# metaPixel-Controller.net
KiCad netlist of a schematic drawn in EAGLE
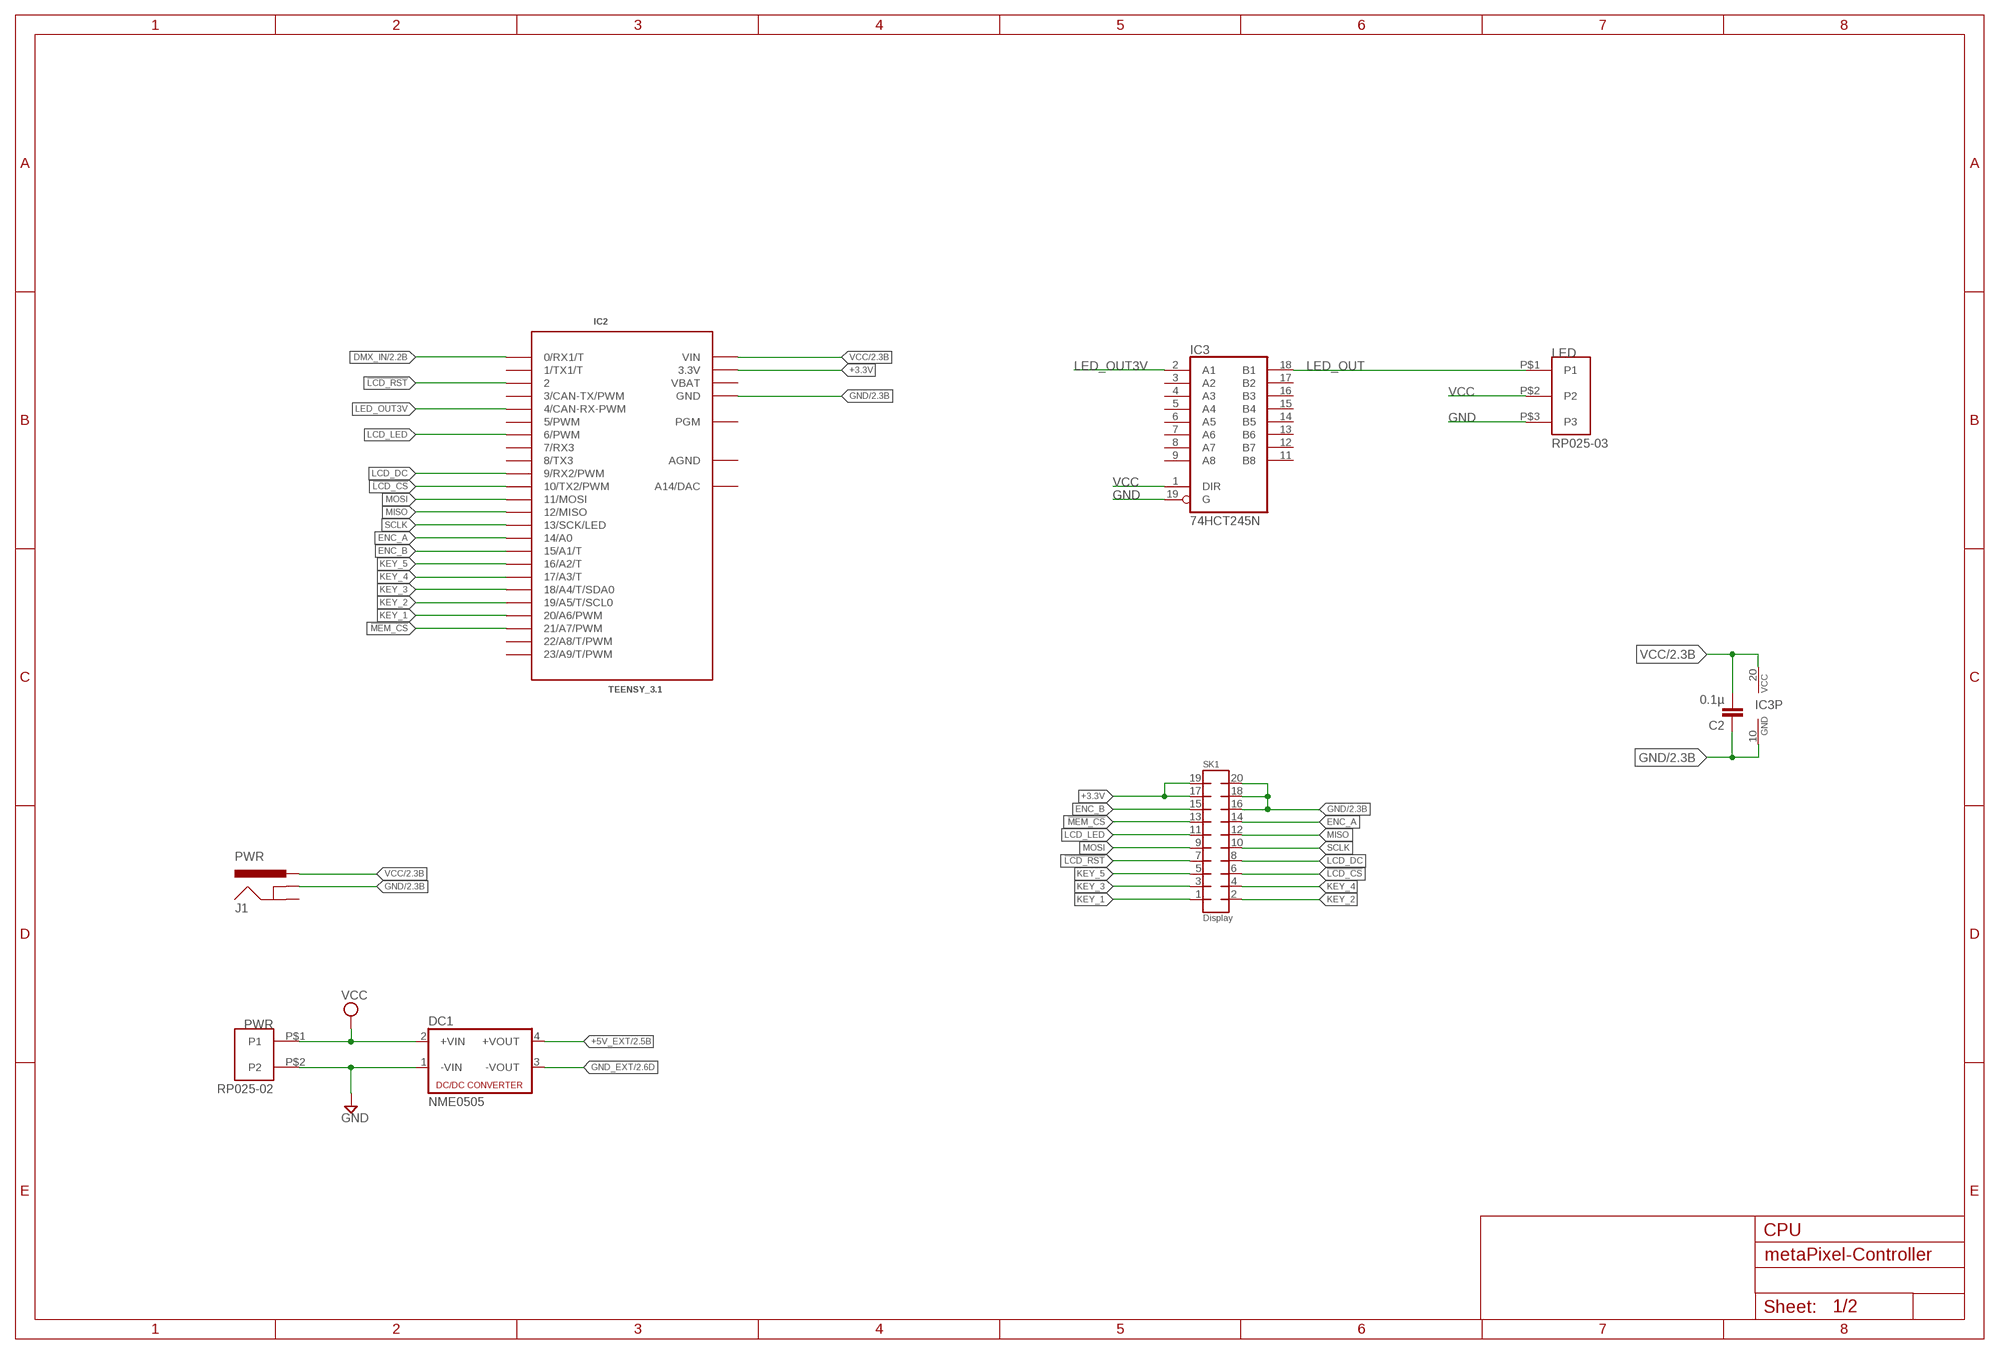
[diagram p0: schematic, sheet 1]
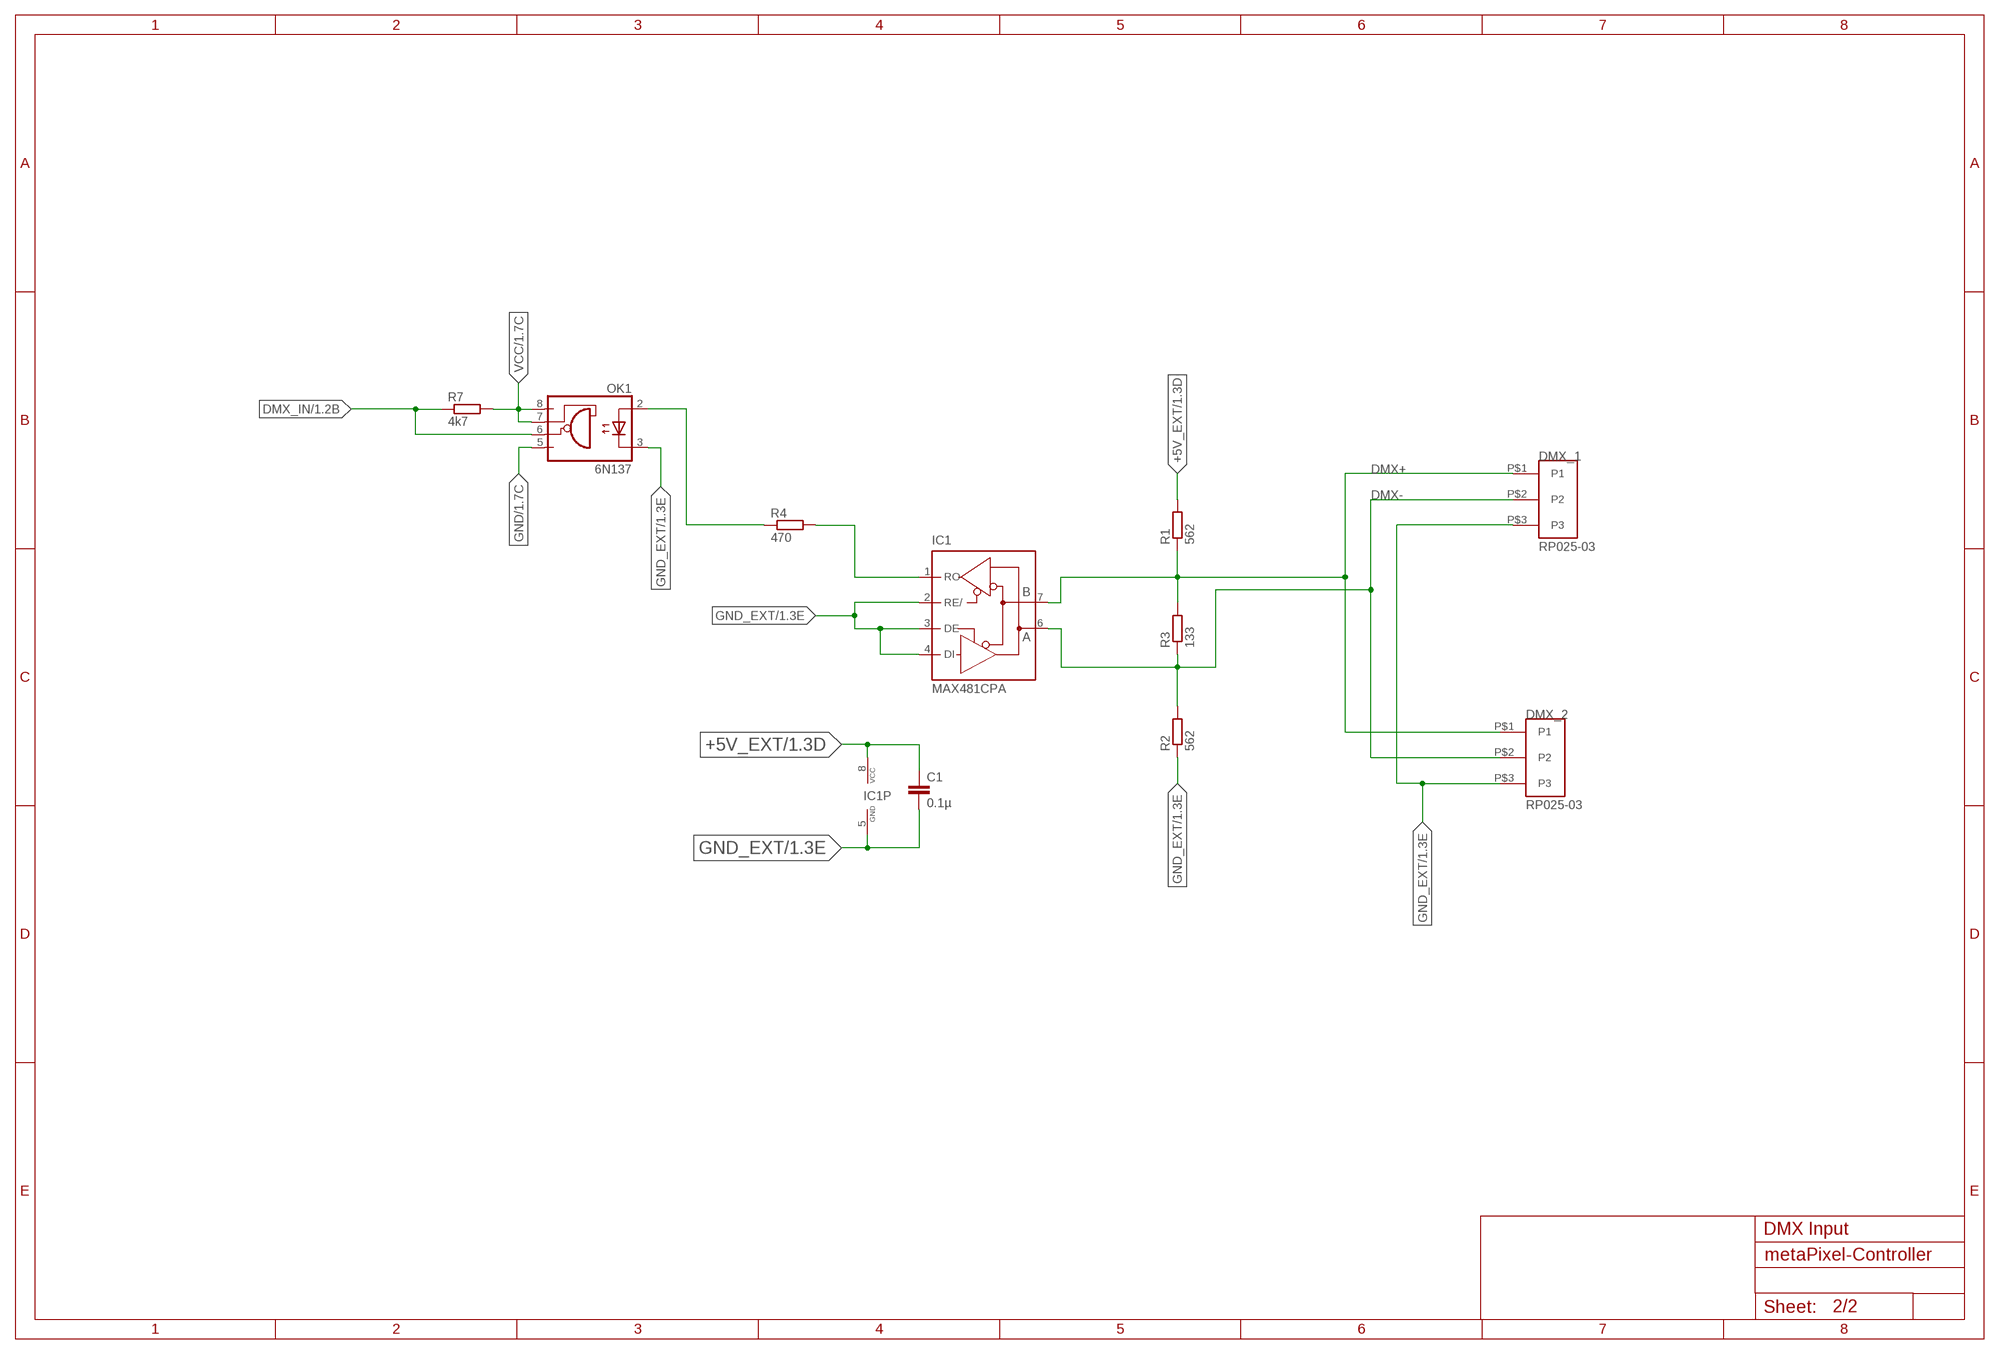
[diagram p1: schematic, sheet 2]

(export (version "E")
  (design (tool "Eeschema 10.0.6"))
  (components
    (comp (ref "C2")
      (value "0.1µ")
      (footprint "eagle-import:C025-030X050")
      (libsource (lib "eagle-import") (part "C-EU025-030X050"))
    )
    (comp (ref "DC1")
      (value "NME0505")
      (footprint "eagle-import:NME")
      (fields (field (name "MF") "C & D TECHNOLOGIES, INC") (field (name "MPN") "NME1205D"))
      (libsource (lib "eagle-import") (part "NME"))
    )
    (comp (ref "IC2")
      (value "TEENSY_3.1")
      (footprint "eagle-import:TEENSY3-OUTER_ROW")
      (libsource (lib "eagle-import") (part "TEENSY_3.1_OUTER_ROW"))
    )
    (comp (ref "IC3")
      (value "74HCT245N")
      (footprint "eagle-import:DIL20")
      (libsource (lib "eagle-import") (part "74245NHCT"))
    )
    (comp (ref "J1")
      (value "PWR")
      (footprint "eagle-import:POWER_JACK_SLOT")
      (libsource (lib "eagle-import") (part "POWER_JACKSLT"))
    )
    (comp (ref "LED")
      (value "RP025-03")
      (footprint "eagle-import:RP025-03")
      (libsource (lib "eagle-import") (part "RP025-03"))
    )
    (comp (ref "PWR")
      (value "RP025-02")
      (footprint "eagle-import:RP025-02")
      (libsource (lib "eagle-import") (part "RP025-02"))
    )
    (comp (ref "SK1")
      (value "Display")
      (footprint "eagle-import:AMP-215079-20")
      (libsource (lib "eagle-import") (part "MMATCH-20-PTH"))
    )
    (comp (ref "C1")
      (value "0.1µ")
      (footprint "eagle-import:C025-030X050")
      (libsource (lib "eagle-import") (part "C-EU025-030X050"))
    )
    (comp (ref "DMX_1")
      (value "RP025-03")
      (footprint "eagle-import:RP025-03")
      (libsource (lib "eagle-import") (part "RP025-03"))
    )
    (comp (ref "DMX_2")
      (value "RP025-03")
      (footprint "eagle-import:RP025-03")
      (libsource (lib "eagle-import") (part "RP025-03"))
    )
    (comp (ref "IC1")
      (value "MAX481CPA")
      (footprint "eagle-import:DIL08")
      (fields (field (name "MPN") "MAX481CPA+"))
      (libsource (lib "eagle-import") (part "MAX481CPA"))
    )
    (comp (ref "OK1")
      (value "6N137")
      (footprint "eagle-import:DIL08")
      (libsource (lib "eagle-import") (part "6N137"))
    )
    (comp (ref "R1")
      (value "562")
      (footprint "eagle-import:0207_7")
      (libsource (lib "eagle-import") (part "resistor_R-EU_0207/7"))
    )
    (comp (ref "R2")
      (value "562")
      (footprint "eagle-import:0207_7")
      (libsource (lib "eagle-import") (part "resistor_R-EU_0207/7"))
    )
    (comp (ref "R3")
      (value "133")
      (footprint "eagle-import:0207_7")
      (libsource (lib "eagle-import") (part "resistor_R-EU_0207/7"))
    )
    (comp (ref "R4")
      (value "470")
      (footprint "eagle-import:0207_10")
      (libsource (lib "eagle-import") (part "R-EU_0207/10"))
    )
    (comp (ref "R7")
      (value "4k7")
      (footprint "eagle-import:0207_10")
      (libsource (lib "eagle-import") (part "resistor_R-EU_0207/10"))
    )
  )
  (nets
    (net (code "1") (name "+3.3V") (class "Default")
      (node (ref "IC2") (pin "3.3V") (pinfunction "3.3V_3.3V") (pintype "power_in"))
      (node (ref "IC2") (pin "3.3V1") (pinfunction "3.3V_3.3V1") (pintype "power_in"))
      (node (ref "SK1") (pin "17") (pinfunction "17_17") (pintype "bidirectional"))
      (node (ref "SK1") (pin "19") (pinfunction "19_19") (pintype "bidirectional"))
    )
    (net (code "2") (name "+5V_EXT") (class "Default")
      (node (ref "C1") (pin "1") (pinfunction "1_1") (pintype "passive"))
      (node (ref "DC1") (pin "4") (pinfunction "+VOUT_4") (pintype "passive"))
      (node (ref "IC1") (pin "8") (pinfunction "VCC_8") (pintype "power_in"))
      (node (ref "R1") (pin "2") (pinfunction "2_2") (pintype "passive"))
    )
    (net (code "3") (name "AGND") (class "Default")
      (node (ref "IC2") (pin "AGND") (pinfunction "AGND_AGND") (pintype "power_in"))
    )
    (net (code "4") (name "DMX+") (class "Default")
      (node (ref "DMX_1") (pin "P$1") (pinfunction "P1_P$1") (pintype "bidirectional"))
      (node (ref "DMX_2") (pin "P$1") (pinfunction "P1_P$1") (pintype "bidirectional"))
      (node (ref "IC1") (pin "7") (pinfunction "B_7") (pintype "passive"))
      (node (ref "R1") (pin "1") (pinfunction "1_1") (pintype "passive"))
      (node (ref "R3") (pin "2") (pinfunction "2_2") (pintype "passive"))
    )
    (net (code "5") (name "DMX-") (class "Default")
      (node (ref "DMX_1") (pin "P$2") (pinfunction "P2_P$2") (pintype "bidirectional"))
      (node (ref "DMX_2") (pin "P$2") (pinfunction "P2_P$2") (pintype "bidirectional"))
      (node (ref "IC1") (pin "6") (pinfunction "A_6") (pintype "passive"))
      (node (ref "R2") (pin "2") (pinfunction "2_2") (pintype "passive"))
      (node (ref "R3") (pin "1") (pinfunction "1_1") (pintype "passive"))
    )
    (net (code "6") (name "DMX_IN") (class "Default")
      (node (ref "IC2") (pin "0") (pinfunction "0/RX1/T_0") (pintype "bidirectional"))
      (node (ref "OK1") (pin "6") (pinfunction "VO_6") (pintype "passive"))
      (node (ref "R7") (pin "1") (pinfunction "1_1") (pintype "passive"))
    )
    (net (code "7") (name "ENC_A") (class "Default")
      (node (ref "IC2") (pin "14/A0") (pinfunction "14/A0_14/A0") (pintype "bidirectional"))
      (node (ref "SK1") (pin "14") (pinfunction "14_14") (pintype "bidirectional"))
    )
    (net (code "8") (name "ENC_B") (class "Default")
      (node (ref "IC2") (pin "15/A1") (pinfunction "15/A1/T_15/A1") (pintype "bidirectional"))
      (node (ref "SK1") (pin "15") (pinfunction "15_15") (pintype "bidirectional"))
    )
    (net (code "9") (name "GND") (class "Default")
      (node (ref "C2") (pin "1") (pinfunction "1_1") (pintype "passive"))
      (node (ref "DC1") (pin "1") (pinfunction "-VIN_1") (pintype "passive"))
      (node (ref "IC2") (pin "GND") (pinfunction "GND_GND") (pintype "power_in"))
      (node (ref "IC2") (pin "GND1") (pinfunction "GND_GND1") (pintype "power_in"))
      (node (ref "IC3") (pin "10") (pinfunction "GND_10") (pintype "power_in"))
      (node (ref "IC3") (pin "19") (pinfunction "G_19") (pintype "input"))
      (node (ref "J1") (pin "GND@1") (pinfunction "GNDBREAK_GND@1") (pintype "bidirectional"))
      (node (ref "LED") (pin "P$3") (pinfunction "P3_P$3") (pintype "bidirectional"))
      (node (ref "OK1") (pin "5") (pinfunction "GND_5") (pintype "passive"))
      (node (ref "PWR") (pin "P$2") (pinfunction "P2_P$2") (pintype "bidirectional"))
      (node (ref "SK1") (pin "16") (pinfunction "16_16") (pintype "bidirectional"))
      (node (ref "SK1") (pin "18") (pinfunction "18_18") (pintype "bidirectional"))
      (node (ref "SK1") (pin "20") (pinfunction "20_20") (pintype "bidirectional"))
    )
    (net (code "10") (name "GND_EXT") (class "Default")
      (node (ref "C1") (pin "2") (pinfunction "2_2") (pintype "passive"))
      (node (ref "DC1") (pin "3") (pinfunction "-VOUT_3") (pintype "passive"))
      (node (ref "DMX_1") (pin "P$3") (pinfunction "P3_P$3") (pintype "bidirectional"))
      (node (ref "DMX_2") (pin "P$3") (pinfunction "P3_P$3") (pintype "bidirectional"))
      (node (ref "IC1") (pin "2") (pinfunction "RE/_2") (pintype "input"))
      (node (ref "IC1") (pin "3") (pinfunction "DE_3") (pintype "input"))
      (node (ref "IC1") (pin "4") (pinfunction "DI_4") (pintype "input"))
      (node (ref "IC1") (pin "5") (pinfunction "GND_5") (pintype "power_in"))
      (node (ref "OK1") (pin "3") (pinfunction "C_3") (pintype "passive"))
      (node (ref "R2") (pin "1") (pinfunction "1_1") (pintype "passive"))
    )
    (net (code "11") (name "KEY_1") (class "Default")
      (node (ref "IC2") (pin "20/A6") (pinfunction "20/A6/PWM_20/A6") (pintype "bidirectional"))
      (node (ref "SK1") (pin "1") (pinfunction "1_1") (pintype "bidirectional"))
    )
    (net (code "12") (name "KEY_2") (class "Default")
      (node (ref "IC2") (pin "19/A5") (pinfunction "19/A5/T/SCL0_19/A5") (pintype "bidirectional"))
      (node (ref "SK1") (pin "2") (pinfunction "2_2") (pintype "bidirectional"))
    )
    (net (code "13") (name "KEY_3") (class "Default")
      (node (ref "IC2") (pin "18/A4") (pinfunction "18/A4/T/SDA0_18/A4") (pintype "bidirectional"))
      (node (ref "SK1") (pin "3") (pinfunction "3_3") (pintype "bidirectional"))
    )
    (net (code "14") (name "KEY_4") (class "Default")
      (node (ref "IC2") (pin "17/A3") (pinfunction "17/A3/T_17/A3") (pintype "bidirectional"))
      (node (ref "SK1") (pin "4") (pinfunction "4_4") (pintype "bidirectional"))
    )
    (net (code "15") (name "KEY_5") (class "Default")
      (node (ref "IC2") (pin "16/A2") (pinfunction "16/A2/T_16/A2") (pintype "bidirectional"))
      (node (ref "SK1") (pin "5") (pinfunction "5_5") (pintype "bidirectional"))
    )
    (net (code "16") (name "LCD_DC") (class "Default")
      (node (ref "IC2") (pin "9") (pinfunction "9/RX2/PWM_9") (pintype "bidirectional"))
      (node (ref "SK1") (pin "8") (pinfunction "8_8") (pintype "bidirectional"))
    )
    (net (code "17") (name "LCD_LED") (class "Default")
      (node (ref "IC2") (pin "6") (pinfunction "6/PWM_6") (pintype "bidirectional"))
      (node (ref "SK1") (pin "11") (pinfunction "11_11") (pintype "bidirectional"))
    )
    (net (code "18") (name "LED_OUT") (class "Default")
      (node (ref "IC3") (pin "18") (pinfunction "B1_18") (pintype "bidirectional"))
      (node (ref "LED") (pin "P$1") (pinfunction "P1_P$1") (pintype "bidirectional"))
    )
    (net (code "19") (name "LED_OUT3V") (class "Default")
      (node (ref "IC2") (pin "4") (pinfunction "4/CAN-RX-PWM_4") (pintype "bidirectional"))
      (node (ref "IC3") (pin "2") (pinfunction "A1_2") (pintype "bidirectional"))
    )
    (net (code "20") (name "MISO") (class "Default")
      (node (ref "IC2") (pin "12") (pinfunction "12/MISO_12") (pintype "bidirectional"))
      (node (ref "SK1") (pin "12") (pinfunction "12_12") (pintype "bidirectional"))
    )
    (net (code "21") (name "MOSI") (class "Default")
      (node (ref "IC2") (pin "11") (pinfunction "11/MOSI_11") (pintype "bidirectional"))
      (node (ref "SK1") (pin "9") (pinfunction "9_9") (pintype "bidirectional"))
    )
    (net (code "22") (name "Net-(IC1A-RO)") (class "Default")
      (node (ref "IC1") (pin "1") (pinfunction "RO_1") (pintype "output"))
      (node (ref "R4") (pin "2") (pinfunction "2_2") (pintype "passive"))
    )
    (net (code "23") (name "Net-(OK1-A)") (class "Default")
      (node (ref "OK1") (pin "2") (pinfunction "A_2") (pintype "passive"))
      (node (ref "R4") (pin "1") (pinfunction "1_1") (pintype "passive"))
    )
    (net (code "24") (name "SCLK") (class "Default")
      (node (ref "IC2") (pin "13") (pinfunction "13/SCK/LED_13") (pintype "bidirectional"))
      (node (ref "SK1") (pin "10") (pinfunction "10_10") (pintype "bidirectional"))
    )
    (net (code "25") (name "VBAT") (class "Default")
      (node (ref "IC2") (pin "VBAT") (pinfunction "VBAT_VBAT") (pintype "power_in"))
    )
    (net (code "26") (name "VCC") (class "Default")
      (node (ref "C2") (pin "2") (pinfunction "2_2") (pintype "passive"))
      (node (ref "DC1") (pin "2") (pinfunction "+VIN_2") (pintype "passive"))
      (node (ref "IC2") (pin "VIN") (pinfunction "VIN_VIN") (pintype "power_in"))
      (node (ref "IC3") (pin "1") (pinfunction "DIR_1") (pintype "input"))
      (node (ref "IC3") (pin "20") (pinfunction "VCC_20") (pintype "power_in"))
      (node (ref "J1") (pin "PWR") (pinfunction "PWR_PWR") (pintype "bidirectional"))
      (node (ref "LED") (pin "P$2") (pinfunction "P2_P$2") (pintype "bidirectional"))
      (node (ref "OK1") (pin "7") (pinfunction "VE_7") (pintype "passive"))
      (node (ref "OK1") (pin "8") (pinfunction "VCC_8") (pintype "passive"))
      (node (ref "PWR") (pin "P$1") (pinfunction "P1_P$1") (pintype "bidirectional"))
      (node (ref "R7") (pin "2") (pinfunction "2_2") (pintype "passive"))
    )
    (net (code "27") (name "unconnected-(IC2-1{slash}TX1{slash}T-Pad1)") (class "Default")
      (node (ref "IC2") (pin "1") (pinfunction "1/TX1/T_1") (pintype "bidirectional"))
    )
    (net (code "28") (name "unconnected-(IC2-3{slash}CAN-TX{slash}PWM-Pad3)") (class "Default")
      (node (ref "IC2") (pin "3") (pinfunction "3/CAN-TX/PWM_3") (pintype "bidirectional"))
    )
    (net (code "29") (name "unconnected-(IC2-5{slash}PWM-Pad5)") (class "Default")
      (node (ref "IC2") (pin "5") (pinfunction "5/PWM_5") (pintype "bidirectional"))
    )
    (net (code "30") (name "unconnected-(IC2-7{slash}RX3-Pad7)") (class "Default")
      (node (ref "IC2") (pin "7") (pinfunction "7/RX3_7") (pintype "bidirectional"))
    )
    (net (code "31") (name "unconnected-(IC2-8{slash}TX3-Pad8)") (class "Default")
      (node (ref "IC2") (pin "8") (pinfunction "8/TX3_8") (pintype "bidirectional"))
    )
    (net (code "32") (name "unconnected-(IC2-22{slash}A8{slash}T{slash}PWM-Pad22{slash}A8)") (class "Default")
      (node (ref "IC2") (pin "22/A8") (pinfunction "22/A8/T/PWM_22/A8") (pintype "bidirectional"))
    )
    (net (code "33") (name "unconnected-(IC2-23{slash}A9{slash}T{slash}PWM-Pad23{slash}A9)") (class "Default")
      (node (ref "IC2") (pin "23/A9") (pinfunction "23/A9/T/PWM_23/A9") (pintype "bidirectional"))
    )
    (net (code "34") (name "unconnected-(IC2-A14{slash}DAC-PadRESET{slash}DAC)") (class "Default")
      (node (ref "IC2") (pin "RESET/DAC") (pinfunction "A14/DAC_RESET/DAC") (pintype "bidirectional"))
    )
    (net (code "35") (name "unconnected-(IC2-PadPGM)") (class "Default")
      (node (ref "IC2") (pin "PGM") (pinfunction "PGM_PGM") (pintype "bidirectional"))
    )
    (net (code "36") (name "unconnected-(IC3A-A2-Pad3)") (class "Default")
      (node (ref "IC3") (pin "3") (pinfunction "A2_3") (pintype "bidirectional"))
    )
    (net (code "37") (name "unconnected-(IC3A-A3-Pad4)") (class "Default")
      (node (ref "IC3") (pin "4") (pinfunction "A3_4") (pintype "bidirectional"))
    )
    (net (code "38") (name "unconnected-(IC3A-A4-Pad5)") (class "Default")
      (node (ref "IC3") (pin "5") (pinfunction "A4_5") (pintype "bidirectional"))
    )
    (net (code "39") (name "unconnected-(IC3A-A5-Pad6)") (class "Default")
      (node (ref "IC3") (pin "6") (pinfunction "A5_6") (pintype "bidirectional"))
    )
    (net (code "40") (name "unconnected-(IC3A-A6-Pad7)") (class "Default")
      (node (ref "IC3") (pin "7") (pinfunction "A6_7") (pintype "bidirectional"))
    )
    (net (code "41") (name "unconnected-(IC3A-A7-Pad8)") (class "Default")
      (node (ref "IC3") (pin "8") (pinfunction "A7_8") (pintype "bidirectional"))
    )
    (net (code "42") (name "unconnected-(IC3A-A8-Pad9)") (class "Default")
      (node (ref "IC3") (pin "9") (pinfunction "A8_9") (pintype "bidirectional"))
    )
    (net (code "43") (name "unconnected-(IC3A-B2-Pad17)") (class "Default")
      (node (ref "IC3") (pin "17") (pinfunction "B2_17") (pintype "bidirectional"))
    )
    (net (code "44") (name "unconnected-(IC3A-B3-Pad16)") (class "Default")
      (node (ref "IC3") (pin "16") (pinfunction "B3_16") (pintype "bidirectional"))
    )
    (net (code "45") (name "unconnected-(IC3A-B4-Pad15)") (class "Default")
      (node (ref "IC3") (pin "15") (pinfunction "B4_15") (pintype "bidirectional"))
    )
    (net (code "46") (name "unconnected-(IC3A-B5-Pad14)") (class "Default")
      (node (ref "IC3") (pin "14") (pinfunction "B5_14") (pintype "bidirectional"))
    )
    (net (code "47") (name "unconnected-(IC3A-B6-Pad13)") (class "Default")
      (node (ref "IC3") (pin "13") (pinfunction "B6_13") (pintype "bidirectional"))
    )
    (net (code "48") (name "unconnected-(IC3A-B7-Pad12)") (class "Default")
      (node (ref "IC3") (pin "12") (pinfunction "B7_12") (pintype "bidirectional"))
    )
    (net (code "49") (name "unconnected-(IC3A-B8-Pad11)") (class "Default")
      (node (ref "IC3") (pin "11") (pinfunction "B8_11") (pintype "bidirectional"))
    )
    (net (code "50") (name "unconnected-(J1-GND-PadGND@2)") (class "Default")
      (node (ref "J1") (pin "GND@2") (pinfunction "GND_GND@2") (pintype "bidirectional"))
    )
    (net (code "51") (name "~{LCD_CS}") (class "Default")
      (node (ref "IC2") (pin "10") (pinfunction "10/TX2/PWM_10") (pintype "bidirectional"))
      (node (ref "SK1") (pin "6") (pinfunction "6_6") (pintype "bidirectional"))
    )
    (net (code "52") (name "~{LCD_RST}") (class "Default")
      (node (ref "IC2") (pin "2") (pinfunction "2_2") (pintype "bidirectional"))
      (node (ref "SK1") (pin "7") (pinfunction "7_7") (pintype "bidirectional"))
    )
    (net (code "53") (name "~{MEM_CS}") (class "Default")
      (node (ref "IC2") (pin "21/A7") (pinfunction "21/A7/PWM_21/A7") (pintype "bidirectional"))
      (node (ref "SK1") (pin "13") (pinfunction "13_13") (pintype "bidirectional"))
    )
  )
)
